# StereoJackToDualDifferential.net
KiCad netlist of a schematic drawn in Altium Designer
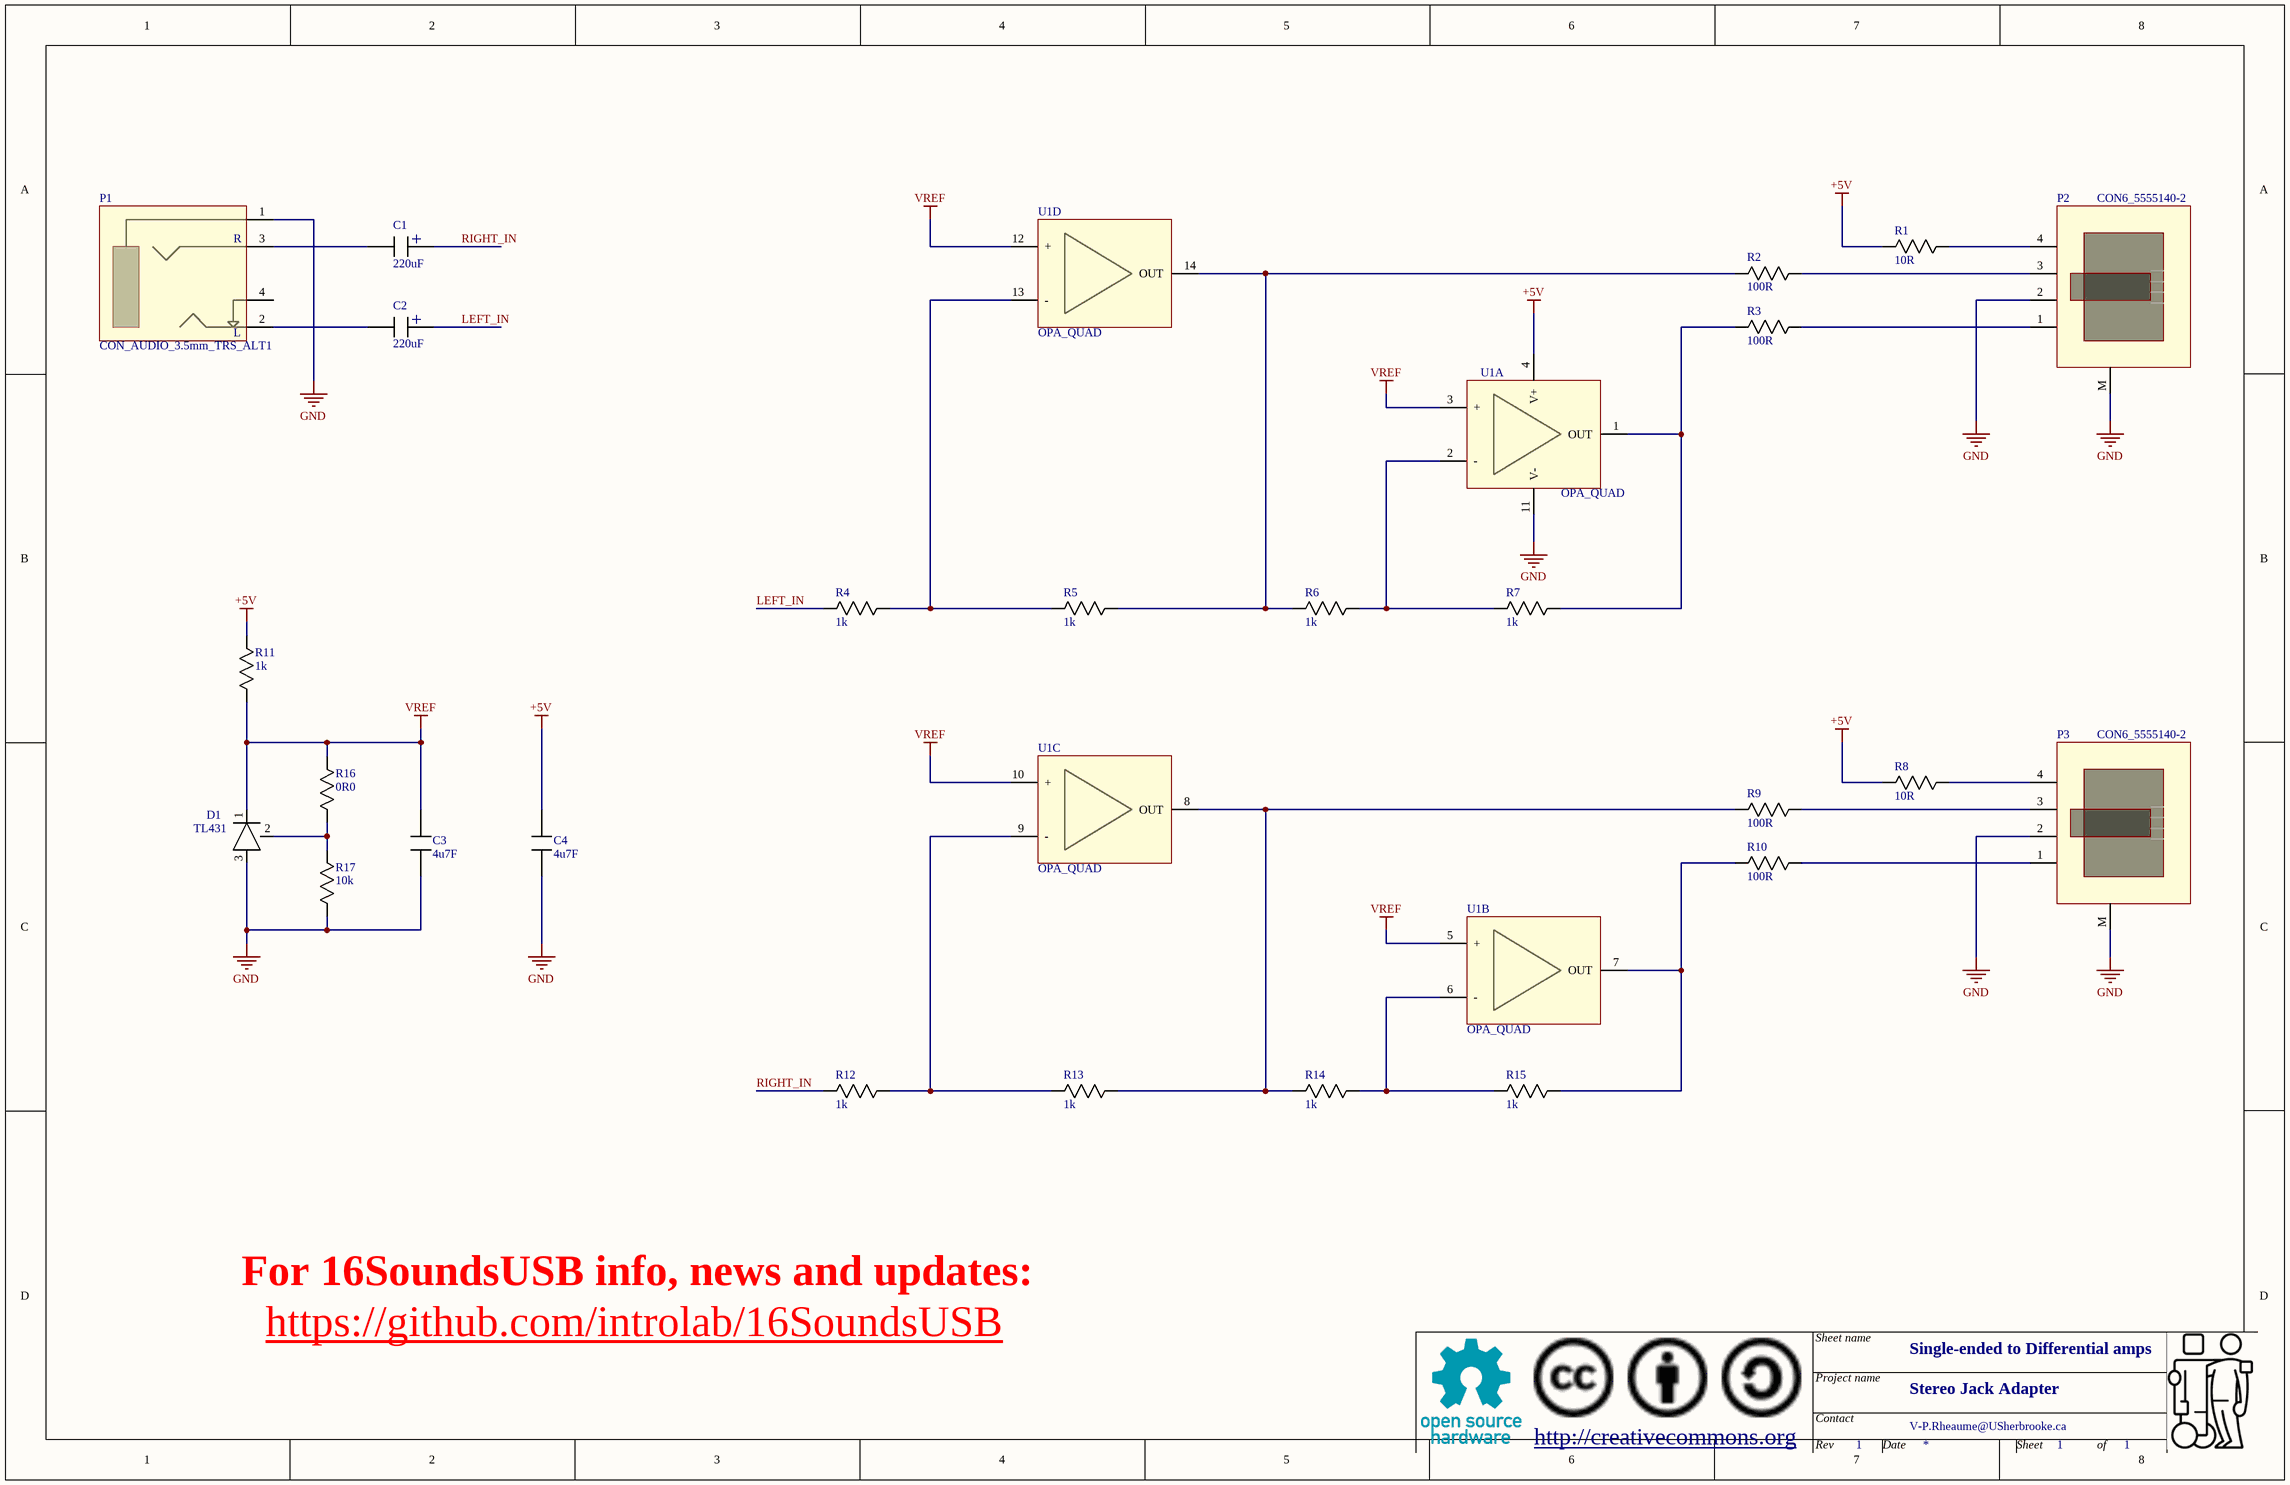
[diagram p0: StereoJackToDualDifferential.SchDoc]

(export (version "E")
  (design (tool "Eeschema 10.0.6"))
  (components
    (comp (ref "C1")
      (value "220uF")
      (footprint "CAP_RAD_SMD_DIA315")
      (description "Capacitor")
      (fields (field (name "MFG") "Nichicon") (field (name "Comment") "Capacitor_Polarized"))
      (libsource (lib "INTER_2014") (part "Capacitor_Polarized"))
    )
    (comp (ref "C2")
      (value "220uF")
      (footprint "CAP_RAD_SMD_DIA315")
      (description "Capacitor")
      (fields (field (name "MFG") "Nichicon") (field (name "Comment") "Capacitor_Polarized"))
      (libsource (lib "INTER_2014") (part "Capacitor_Polarized"))
    )
    (comp (ref "C3")
      (value "4u7F")
      (footprint "0805")
      (description "Capacitor")
      (fields (field (name "MFG") "Wurth"))
      (libsource (lib "INTER_2014") (part "Capacitor"))
    )
    (comp (ref "C4")
      (value "4u7F")
      (footprint "0805")
      (description "Capacitor")
      (fields (field (name "MFG") "Wurth"))
      (libsource (lib "INTER_2014") (part "Capacitor"))
    )
    (comp (ref "D1")
      (value "TL431")
      (footprint "SOT23_132")
      (fields (field (name "MFG") "NXP"))
      (libsource (lib "INTER_2014") (part "TL431"))
    )
    (comp (ref "P1")
      (value "CON_AUDIO_3.5mm_TRS_ALT1")
      (footprint "CONN_3.5mm_CUI 3523-SMT")
      (description "Audio 3.5mm CUI SJ-3523-SMT-TR")
      (fields (field (name "MFG") "CUI"))
      (libsource (lib "INTER_2014") (part "CON_AUDIO_3.5mm_TRS_ALT1"))
    )
    (comp (ref "P2")
      (value "CON6_5555140-2")
      (footprint "CONN4_5555140-2")
      (description "6p4c RJ11/RJ14, shielded (5555165-2 unshielded)")
      (fields (field (name "MFG") "TE"))
      (libsource (lib "INTER_2014") (part "CON6_5555140-2"))
    )
    (comp (ref "P3")
      (value "CON6_5555140-2")
      (footprint "CONN4_5555140-2")
      (description "6p4c RJ11/RJ14, shielded (5555165-2 unshielded)")
      (fields (field (name "MFG") "TE"))
      (libsource (lib "INTER_2014") (part "CON6_5555140-2"))
    )
    (comp (ref "R1")
      (value "10R")
      (footprint "0805")
      (description "Resistor")
      (fields (field (name "MFG") "Stackpole"))
      (libsource (lib "INTER_2014") (part "Resistor"))
    )
    (comp (ref "R2")
      (value "100R")
      (footprint "0805")
      (description "Resistor")
      (fields (field (name "MFG") "Stackpole"))
      (libsource (lib "INTER_2014") (part "Resistor"))
    )
    (comp (ref "R3")
      (value "100R")
      (footprint "0805")
      (description "Resistor")
      (fields (field (name "MFG") "Stackpole"))
      (libsource (lib "INTER_2014") (part "Resistor"))
    )
    (comp (ref "R4")
      (value "1k")
      (footprint "0805")
      (description "Resistor")
      (fields (field (name "MFG") "Stackpole"))
      (libsource (lib "INTER_2014") (part "Resistor"))
    )
    (comp (ref "R5")
      (value "1k")
      (footprint "0805")
      (description "Resistor")
      (fields (field (name "MFG") "Stackpole"))
      (libsource (lib "INTER_2014") (part "Resistor"))
    )
    (comp (ref "R6")
      (value "1k")
      (footprint "0805")
      (description "Resistor")
      (fields (field (name "MFG") "Stackpole"))
      (libsource (lib "INTER_2014") (part "Resistor"))
    )
    (comp (ref "R7")
      (value "1k")
      (footprint "0805")
      (description "Resistor")
      (fields (field (name "MFG") "Stackpole"))
      (libsource (lib "INTER_2014") (part "Resistor"))
    )
    (comp (ref "R8")
      (value "10R")
      (footprint "0805")
      (description "Resistor")
      (fields (field (name "MFG") "Stackpole"))
      (libsource (lib "INTER_2014") (part "Resistor"))
    )
    (comp (ref "R9")
      (value "100R")
      (footprint "0805")
      (description "Resistor")
      (fields (field (name "MFG") "Stackpole"))
      (libsource (lib "INTER_2014") (part "Resistor"))
    )
    (comp (ref "R10")
      (value "100R")
      (footprint "0805")
      (description "Resistor")
      (fields (field (name "MFG") "Stackpole"))
      (libsource (lib "INTER_2014") (part "Resistor"))
    )
    (comp (ref "R11")
      (value "1k")
      (footprint "0805")
      (description "Resistor")
      (fields (field (name "MFG") "Stackpole"))
      (libsource (lib "INTER_2014") (part "Resistor"))
    )
    (comp (ref "R12")
      (value "1k")
      (footprint "0805")
      (description "Resistor")
      (fields (field (name "MFG") "Stackpole"))
      (libsource (lib "INTER_2014") (part "Resistor"))
    )
    (comp (ref "R13")
      (value "1k")
      (footprint "0805")
      (description "Resistor")
      (fields (field (name "MFG") "Stackpole"))
      (libsource (lib "INTER_2014") (part "Resistor"))
    )
    (comp (ref "R14")
      (value "1k")
      (footprint "0805")
      (description "Resistor")
      (fields (field (name "MFG") "Stackpole"))
      (libsource (lib "INTER_2014") (part "Resistor"))
    )
    (comp (ref "R15")
      (value "1k")
      (footprint "0805")
      (description "Resistor")
      (fields (field (name "MFG") "Stackpole"))
      (libsource (lib "INTER_2014") (part "Resistor"))
    )
    (comp (ref "R16")
      (value "0R0")
      (footprint "0805")
      (description "Resistor")
      (fields (field (name "MFG") "Bourns"))
      (libsource (lib "INTER_2014") (part "Resistor"))
    )
    (comp (ref "R17")
      (value "10k")
      (footprint "0805")
      (description "Resistor")
      (fields (field (name "MFG") "Stackpole"))
      (libsource (lib "INTER_2014") (part "Resistor"))
    )
    (comp (ref "U1")
      (value "OPA_QUAD")
      (footprint "TSSOP14")
      (description "Quad amplifier (standard)")
      (fields (field (name "MFG") "Microchip"))
      (libsource (lib "INTER_2014") (part "OPA_QUAD"))
    )
  )
  (nets
    (net (code "1") (name "+5V") (class "Default")
      (node (ref "C4") (pin "1") (pintype "passive"))
      (node (ref "R1") (pin "2") (pintype "passive"))
      (node (ref "R11") (pin "2") (pintype "passive"))
      (node (ref "R8") (pin "2") (pintype "passive"))
      (node (ref "U1") (pin "4") (pinfunction "V+_4") (pintype "passive"))
    )
    (net (code "2") (name "/LEFT_IN") (class "Default")
      (node (ref "C2") (pin "+") (pintype "passive"))
      (node (ref "R4") (pin "2") (pintype "passive"))
    )
    (net (code "3") (name "/RIGHT_IN") (class "Default")
      (node (ref "C1") (pin "+") (pintype "passive"))
      (node (ref "R12") (pin "2") (pintype "passive"))
    )
    (net (code "4") (name "GND") (class "Default")
      (node (ref "C3") (pin "2") (pintype "passive"))
      (node (ref "C4") (pin "2") (pintype "passive"))
      (node (ref "D1") (pin "3") (pintype "passive"))
      (node (ref "P1") (pin "1") (pintype "passive"))
      (node (ref "P2") (pin "2") (pintype "passive"))
      (node (ref "P2") (pin "M") (pintype "passive"))
      (node (ref "P3") (pin "2") (pintype "passive"))
      (node (ref "P3") (pin "M") (pintype "passive"))
      (node (ref "R17") (pin "1") (pintype "passive"))
      (node (ref "U1") (pin "11") (pinfunction "V-_11") (pintype "passive"))
    )
    (net (code "5") (name "Net-(D1-Pad2)") (class "Default")
      (node (ref "D1") (pin "2") (pintype "passive"))
      (node (ref "R16") (pin "1") (pintype "passive"))
      (node (ref "R17") (pin "2") (pintype "passive"))
    )
    (net (code "6") (name "Net-(P1-L)") (class "Default")
      (node (ref "C2") (pin "-") (pintype "passive"))
      (node (ref "P1") (pin "2") (pinfunction "L_2") (pintype "passive"))
    )
    (net (code "7") (name "Net-(P1-R)") (class "Default")
      (node (ref "C1") (pin "-") (pintype "passive"))
      (node (ref "P1") (pin "3") (pinfunction "R_3") (pintype "passive"))
    )
    (net (code "8") (name "Net-(P2-Pad1)") (class "Default")
      (node (ref "P2") (pin "1") (pintype "passive"))
      (node (ref "R3") (pin "2") (pintype "passive"))
    )
    (net (code "9") (name "Net-(P2-Pad3)") (class "Default")
      (node (ref "P2") (pin "3") (pintype "passive"))
      (node (ref "R2") (pin "2") (pintype "passive"))
    )
    (net (code "10") (name "Net-(P2-Pad4)") (class "Default")
      (node (ref "P2") (pin "4") (pintype "passive"))
      (node (ref "R1") (pin "1") (pintype "passive"))
    )
    (net (code "11") (name "Net-(P3-Pad1)") (class "Default")
      (node (ref "P3") (pin "1") (pintype "passive"))
      (node (ref "R10") (pin "2") (pintype "passive"))
    )
    (net (code "12") (name "Net-(P3-Pad3)") (class "Default")
      (node (ref "P3") (pin "3") (pintype "passive"))
      (node (ref "R9") (pin "2") (pintype "passive"))
    )
    (net (code "13") (name "Net-(P3-Pad4)") (class "Default")
      (node (ref "P3") (pin "4") (pintype "passive"))
      (node (ref "R8") (pin "1") (pintype "passive"))
    )
    (net (code "14") (name "Net-(U1A--)") (class "Default")
      (node (ref "R6") (pin "2") (pintype "passive"))
      (node (ref "R7") (pin "1") (pintype "passive"))
      (node (ref "U1") (pin "2") (pinfunction "-_2") (pintype "passive"))
    )
    (net (code "15") (name "Net-(U1A-OUT)") (class "Default")
      (node (ref "R3") (pin "1") (pintype "passive"))
      (node (ref "R7") (pin "2") (pintype "passive"))
      (node (ref "U1") (pin "1") (pinfunction "OUT_1") (pintype "passive"))
    )
    (net (code "16") (name "Net-(U1B--)") (class "Default")
      (node (ref "R14") (pin "2") (pintype "passive"))
      (node (ref "R15") (pin "1") (pintype "passive"))
      (node (ref "U1") (pin "6") (pinfunction "-_6") (pintype "passive"))
    )
    (net (code "17") (name "Net-(U1B-OUT)") (class "Default")
      (node (ref "R10") (pin "1") (pintype "passive"))
      (node (ref "R15") (pin "2") (pintype "passive"))
      (node (ref "U1") (pin "7") (pinfunction "OUT_7") (pintype "passive"))
    )
    (net (code "18") (name "Net-(U1C--)") (class "Default")
      (node (ref "R12") (pin "1") (pintype "passive"))
      (node (ref "R13") (pin "2") (pintype "passive"))
      (node (ref "U1") (pin "9") (pinfunction "-_9") (pintype "passive"))
    )
    (net (code "19") (name "Net-(U1C-OUT)") (class "Default")
      (node (ref "R13") (pin "1") (pintype "passive"))
      (node (ref "R14") (pin "1") (pintype "passive"))
      (node (ref "R9") (pin "1") (pintype "passive"))
      (node (ref "U1") (pin "8") (pinfunction "OUT_8") (pintype "passive"))
    )
    (net (code "20") (name "Net-(U1D--)") (class "Default")
      (node (ref "R4") (pin "1") (pintype "passive"))
      (node (ref "R5") (pin "2") (pintype "passive"))
      (node (ref "U1") (pin "13") (pinfunction "-_13") (pintype "passive"))
    )
    (net (code "21") (name "Net-(U1D-OUT)") (class "Default")
      (node (ref "R2") (pin "1") (pintype "passive"))
      (node (ref "R5") (pin "1") (pintype "passive"))
      (node (ref "R6") (pin "1") (pintype "passive"))
      (node (ref "U1") (pin "14") (pinfunction "OUT_14") (pintype "passive"))
    )
    (net (code "22") (name "VREF") (class "Default")
      (node (ref "C3") (pin "1") (pintype "passive"))
      (node (ref "D1") (pin "1") (pintype "passive"))
      (node (ref "R11") (pin "1") (pintype "passive"))
      (node (ref "R16") (pin "2") (pintype "passive"))
      (node (ref "U1") (pin "10") (pinfunction "+_10") (pintype "passive"))
      (node (ref "U1") (pin "12") (pinfunction "+_12") (pintype "passive"))
      (node (ref "U1") (pin "3") (pinfunction "+_3") (pintype "passive"))
      (node (ref "U1") (pin "5") (pinfunction "+_5") (pintype "passive"))
    )
    (net (code "23") (name "unconnected-(P1-NC_L-Pad4)") (class "Default")
      (node (ref "P1") (pin "4") (pinfunction "NC_L_4") (pintype "passive"))
    )
  )
)
